# ResSelect.net
KiCad netlist of a schematic drawn in Altium Designer
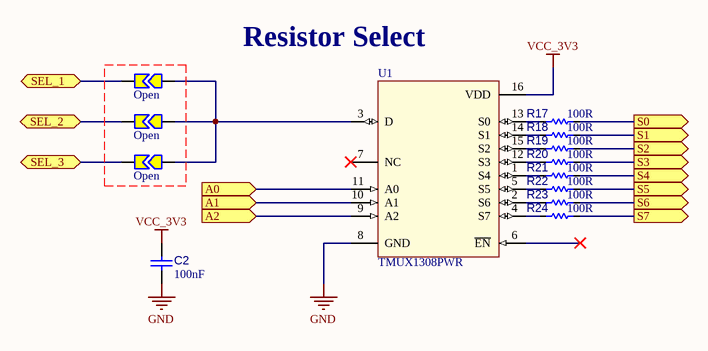
[diagram p0: ResSelect.SchDoc]

(export (version "E")
  (design (tool "Eeschema 10.0.6"))
  (components
    (comp (ref "C2")
      (value "100nF")
      (footprint "C_1608[0603]")
      (description "Capacitor type 1")
      (fields (field (name "TOLERANCE") "10%") (field (name "Comment") "CAP CER 100nF 50V 0603"))
      (libsource (lib "TEP-AltiumLib-Passives-RLC") (part "capacitor"))
    )
    (comp (ref "R17")
      (value "100R")
      (footprint "R_1608[0603]")
      (description "Resistor type 1")
      (fields (field (name "TOLERANCE") "1%") (field (name "Comment") "Res 100R 1% 0603"))
      (libsource (lib "TEP-AltiumLib-Passives-RLC") (part "resistor"))
    )
    (comp (ref "R18")
      (value "100R")
      (footprint "R_1608[0603]")
      (description "Resistor type 1")
      (fields (field (name "TOLERANCE") "1%") (field (name "Comment") "Res 100R 1% 0603"))
      (libsource (lib "TEP-AltiumLib-Passives-RLC") (part "resistor"))
    )
    (comp (ref "R19")
      (value "100R")
      (footprint "R_1608[0603]")
      (description "Resistor type 1")
      (fields (field (name "TOLERANCE") "1%") (field (name "Comment") "Res 100R 1% 0603"))
      (libsource (lib "TEP-AltiumLib-Passives-RLC") (part "resistor"))
    )
    (comp (ref "R20")
      (value "100R")
      (footprint "R_1608[0603]")
      (description "Resistor type 1")
      (fields (field (name "TOLERANCE") "1%") (field (name "Comment") "Res 100R 1% 0603"))
      (libsource (lib "TEP-AltiumLib-Passives-RLC") (part "resistor"))
    )
    (comp (ref "R21")
      (value "100R")
      (footprint "R_1608[0603]")
      (description "Resistor type 1")
      (fields (field (name "TOLERANCE") "1%") (field (name "Comment") "Res 100R 1% 0603"))
      (libsource (lib "TEP-AltiumLib-Passives-RLC") (part "resistor"))
    )
    (comp (ref "R22")
      (value "100R")
      (footprint "R_1608[0603]")
      (description "Resistor type 1")
      (fields (field (name "TOLERANCE") "1%") (field (name "Comment") "Res 100R 1% 0603"))
      (libsource (lib "TEP-AltiumLib-Passives-RLC") (part "resistor"))
    )
    (comp (ref "R23")
      (value "100R")
      (footprint "R_1608[0603]")
      (description "Resistor type 1")
      (fields (field (name "TOLERANCE") "1%") (field (name "Comment") "Res 100R 1% 0603"))
      (libsource (lib "TEP-AltiumLib-Passives-RLC") (part "resistor"))
    )
    (comp (ref "R24")
      (value "100R")
      (footprint "R_1608[0603]")
      (description "Resistor type 1")
      (fields (field (name "TOLERANCE") "1%") (field (name "Comment") "Res 100R 1% 0603"))
      (libsource (lib "TEP-AltiumLib-Passives-RLC") (part "resistor"))
    )
    (comp (ref "SB1")
      (value "Open")
      (footprint "SB-TINY-OPEN")
      (description "Solder Jumper")
      (libsource (lib "TEP-AltiumLib-Hardware") (part "Solder-Jumper-Open"))
    )
    (comp (ref "SB2")
      (value "Open")
      (footprint "SB-TINY-OPEN")
      (description "Solder Jumper")
      (libsource (lib "TEP-AltiumLib-Hardware") (part "Solder-Jumper-Open"))
    )
    (comp (ref "SB3")
      (value "Open")
      (footprint "SB-TINY-OPEN")
      (description "Solder Jumper")
      (libsource (lib "TEP-AltiumLib-Hardware") (part "Solder-Jumper-Open"))
    )
    (comp (ref "U1")
      (value "TMUX1308PWR")
      (footprint "U_TSSOP65P500X450-16")
      (description "IC MUX 8:1 195OHM 16TSSOP")
      (libsource (lib "TEP-AltiumLib-ICs") (part "U_TMUX1308PWR"))
    )
  )
  (nets
    (net (code "1") (name "/A0") (class "Default")
      (node (ref "U1") (pin "11") (pinfunction "A0_11") (pintype "input"))
    )
    (net (code "2") (name "/A1") (class "Default")
      (node (ref "U1") (pin "10") (pinfunction "A1_10") (pintype "input"))
    )
    (net (code "3") (name "/A2") (class "Default")
      (node (ref "U1") (pin "9") (pinfunction "A2_9") (pintype "input"))
    )
    (net (code "4") (name "/S0") (class "Default")
      (node (ref "R17") (pin "2") (pinfunction "2_2") (pintype "passive"))
    )
    (net (code "5") (name "/S1") (class "Default")
      (node (ref "R18") (pin "2") (pinfunction "2_2") (pintype "passive"))
    )
    (net (code "6") (name "/S2") (class "Default")
      (node (ref "R19") (pin "2") (pinfunction "2_2") (pintype "passive"))
    )
    (net (code "7") (name "/S3") (class "Default")
      (node (ref "R20") (pin "2") (pinfunction "2_2") (pintype "passive"))
    )
    (net (code "8") (name "/S4") (class "Default")
      (node (ref "R21") (pin "2") (pinfunction "2_2") (pintype "passive"))
    )
    (net (code "9") (name "/S5") (class "Default")
      (node (ref "R22") (pin "2") (pinfunction "2_2") (pintype "passive"))
    )
    (net (code "10") (name "/S6") (class "Default")
      (node (ref "R23") (pin "2") (pinfunction "2_2") (pintype "passive"))
    )
    (net (code "11") (name "/S7") (class "Default")
      (node (ref "R24") (pin "2") (pinfunction "2_2") (pintype "passive"))
    )
    (net (code "12") (name "/SEL_1") (class "Default")
      (node (ref "SB1") (pin "2") (pinfunction "2_2") (pintype "passive"))
    )
    (net (code "13") (name "/SEL_2") (class "Default")
      (node (ref "SB2") (pin "2") (pinfunction "2_2") (pintype "passive"))
    )
    (net (code "14") (name "/SEL_3") (class "Default")
      (node (ref "SB3") (pin "2") (pinfunction "2_2") (pintype "passive"))
    )
    (net (code "15") (name "GND") (class "Default")
      (node (ref "C2") (pin "1") (pinfunction "1_1") (pintype "passive"))
      (node (ref "U1") (pin "8") (pinfunction "GND_8") (pintype "power_in"))
    )
    (net (code "16") (name "Net-(U1-D)") (class "Default")
      (node (ref "SB1") (pin "1") (pinfunction "1_1") (pintype "passive"))
      (node (ref "SB2") (pin "1") (pinfunction "1_1") (pintype "passive"))
      (node (ref "SB3") (pin "1") (pinfunction "1_1") (pintype "passive"))
      (node (ref "U1") (pin "3") (pinfunction "D_3") (pintype "bidirectional"))
    )
    (net (code "17") (name "Net-(U1-S0)") (class "Default")
      (node (ref "R17") (pin "1") (pinfunction "1_1") (pintype "passive"))
      (node (ref "U1") (pin "13") (pinfunction "S0_13") (pintype "bidirectional"))
    )
    (net (code "18") (name "Net-(U1-S1)") (class "Default")
      (node (ref "R18") (pin "1") (pinfunction "1_1") (pintype "passive"))
      (node (ref "U1") (pin "14") (pinfunction "S1_14") (pintype "bidirectional"))
    )
    (net (code "19") (name "Net-(U1-S2)") (class "Default")
      (node (ref "R19") (pin "1") (pinfunction "1_1") (pintype "passive"))
      (node (ref "U1") (pin "15") (pinfunction "S2_15") (pintype "bidirectional"))
    )
    (net (code "20") (name "Net-(U1-S3)") (class "Default")
      (node (ref "R20") (pin "1") (pinfunction "1_1") (pintype "passive"))
      (node (ref "U1") (pin "12") (pinfunction "S3_12") (pintype "bidirectional"))
    )
    (net (code "21") (name "Net-(U1-S4)") (class "Default")
      (node (ref "R21") (pin "1") (pinfunction "1_1") (pintype "passive"))
      (node (ref "U1") (pin "1") (pinfunction "S4_1") (pintype "bidirectional"))
    )
    (net (code "22") (name "Net-(U1-S5)") (class "Default")
      (node (ref "R22") (pin "1") (pinfunction "1_1") (pintype "passive"))
      (node (ref "U1") (pin "5") (pinfunction "S5_5") (pintype "bidirectional"))
    )
    (net (code "23") (name "Net-(U1-S6)") (class "Default")
      (node (ref "R23") (pin "1") (pinfunction "1_1") (pintype "passive"))
      (node (ref "U1") (pin "2") (pinfunction "S6_2") (pintype "bidirectional"))
    )
    (net (code "24") (name "Net-(U1-S7)") (class "Default")
      (node (ref "R24") (pin "1") (pinfunction "1_1") (pintype "passive"))
      (node (ref "U1") (pin "4") (pinfunction "S7_4") (pintype "bidirectional"))
    )
    (net (code "25") (name "VCC_3V3") (class "Default")
      (node (ref "C2") (pin "2") (pinfunction "2_2") (pintype "passive"))
      (node (ref "U1") (pin "16") (pinfunction "VDD_16") (pintype "power_in"))
    )
    (net (code "26") (name "unconnected-(U1-NC-Pad7)") (class "Default")
      (node (ref "U1") (pin "7") (pinfunction "NC_7") (pintype "passive+no_connect"))
    )
    (net (code "27") (name "unconnected-(U1-~{EN}-Pad6)") (class "Default")
      (node (ref "U1") (pin "6") (pinfunction "~{EN}_6") (pintype "input+no_connect"))
    )
  )
)
